# Rp2040.net
KiCad netlist of a schematic drawn in Altium Designer
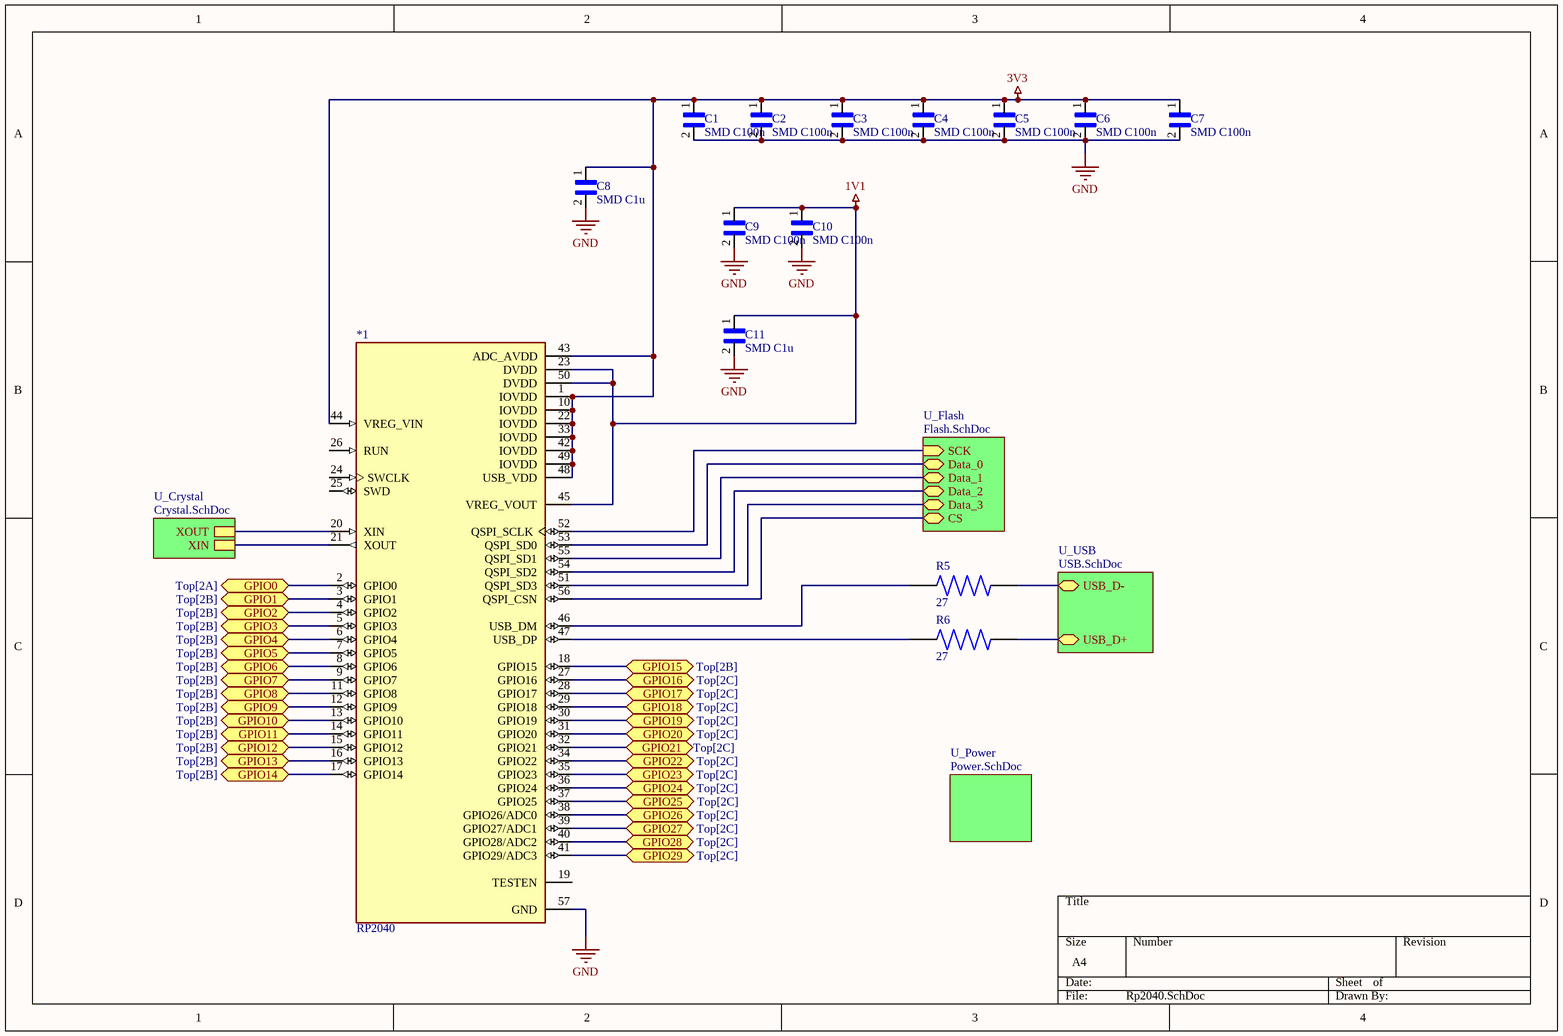
[diagram p0: Rp2040.SchDoc]

(export (version "E")
  (design (tool "Eeschema 10.0.6"))
  (components
    (comp (ref "*1")
      (value "RP2040")
      (footprint "RP2040-Footprint-1")
      (description "Microprocessor")
      (libsource (lib "Tobias") (part "RP2040-Symbol-1"))
    )
    (comp (ref "C1")
      (value "SMD C100n")
      (footprint "SMD Capacetor-Footprint-1")
      (description "Generic SMD Capacetor")
      (libsource (lib "Tobias") (part "100n"))
    )
    (comp (ref "C2")
      (value "SMD C100n")
      (footprint "SMD Capacetor-Footprint-1")
      (description "Generic SMD Capacetor")
      (libsource (lib "Tobias") (part "100n"))
    )
    (comp (ref "C3")
      (value "SMD C100n")
      (footprint "SMD Capacetor-Footprint-1")
      (description "Generic SMD Capacetor")
      (libsource (lib "Tobias") (part "100n"))
    )
    (comp (ref "C4")
      (value "SMD C100n")
      (footprint "SMD Capacetor-Footprint-1")
      (description "Generic SMD Capacetor")
      (libsource (lib "Tobias") (part "100n"))
    )
    (comp (ref "C5")
      (value "SMD C100n")
      (footprint "SMD Capacetor-Footprint-1")
      (description "Generic SMD Capacetor")
      (libsource (lib "Tobias") (part "100n"))
    )
    (comp (ref "C6")
      (value "SMD C100n")
      (footprint "SMD Capacetor-Footprint-1")
      (description "Generic SMD Capacetor")
      (libsource (lib "Tobias") (part "100n"))
    )
    (comp (ref "C7")
      (value "SMD C100n")
      (footprint "SMD Capacetor-Footprint-1")
      (description "Generic SMD Capacetor")
      (libsource (lib "Tobias") (part "100n"))
    )
    (comp (ref "C8")
      (value "SMD C1u")
      (footprint "SMD Capacetor-Footprint-1")
      (description "Generic SMD Capacetor")
      (libsource (lib "Tobias") (part "1u"))
    )
    (comp (ref "C9")
      (value "SMD C100n")
      (footprint "SMD Capacetor-Footprint-1")
      (description "Generic SMD Capacetor")
      (libsource (lib "Tobias") (part "100n"))
    )
    (comp (ref "C10")
      (value "SMD C100n")
      (footprint "SMD Capacetor-Footprint-1")
      (description "Generic SMD Capacetor")
      (libsource (lib "Tobias") (part "100n"))
    )
    (comp (ref "C11")
      (value "SMD C1u")
      (footprint "SMD Capacetor-Footprint-1")
      (description "Generic SMD Capacetor")
      (libsource (lib "Tobias") (part "1u"))
    )
    (comp (ref "R5")
      (value "27")
      (footprint "SMD Resistor-Footprint-1")
      (description "Generic SMD Resistor")
      (libsource (lib "Tobias") (part "SMD Resistor-Symbol-1"))
    )
    (comp (ref "R6")
      (value "27")
      (footprint "SMD Resistor-Footprint-1")
      (description "Generic SMD Resistor")
      (libsource (lib "Tobias") (part "SMD Resistor-Symbol-1"))
    )
  )
  (nets
    (net (code "1") (name "/CS") (class "Default")
      (node (ref "*1") (pin "56") (pinfunction "QSPI_CSN_56") (pintype "bidirectional"))
    )
    (net (code "2") (name "/Data_0") (class "Default")
      (node (ref "*1") (pin "53") (pinfunction "QSPI_SD0_53") (pintype "bidirectional"))
    )
    (net (code "3") (name "/Data_1") (class "Default")
      (node (ref "*1") (pin "55") (pinfunction "QSPI_SD1_55") (pintype "bidirectional"))
    )
    (net (code "4") (name "/Data_2") (class "Default")
      (node (ref "*1") (pin "54") (pinfunction "QSPI_SD2_54") (pintype "bidirectional"))
    )
    (net (code "5") (name "/Data_3") (class "Default")
      (node (ref "*1") (pin "51") (pinfunction "QSPI_SD3_51") (pintype "bidirectional"))
    )
    (net (code "6") (name "/GPIO0") (class "Default")
      (node (ref "*1") (pin "2") (pinfunction "GPIO0_2") (pintype "bidirectional"))
    )
    (net (code "7") (name "/GPIO1") (class "Default")
      (node (ref "*1") (pin "3") (pinfunction "GPIO1_3") (pintype "bidirectional"))
    )
    (net (code "8") (name "/GPIO2") (class "Default")
      (node (ref "*1") (pin "4") (pinfunction "GPIO2_4") (pintype "bidirectional"))
    )
    (net (code "9") (name "/GPIO3") (class "Default")
      (node (ref "*1") (pin "5") (pinfunction "GPIO3_5") (pintype "bidirectional"))
    )
    (net (code "10") (name "/GPIO4") (class "Default")
      (node (ref "*1") (pin "6") (pinfunction "GPIO4_6") (pintype "bidirectional"))
    )
    (net (code "11") (name "/GPIO5") (class "Default")
      (node (ref "*1") (pin "7") (pinfunction "GPIO5_7") (pintype "bidirectional"))
    )
    (net (code "12") (name "/GPIO6") (class "Default")
      (node (ref "*1") (pin "8") (pinfunction "GPIO6_8") (pintype "bidirectional"))
    )
    (net (code "13") (name "/GPIO7") (class "Default")
      (node (ref "*1") (pin "9") (pinfunction "GPIO7_9") (pintype "bidirectional"))
    )
    (net (code "14") (name "/GPIO8") (class "Default")
      (node (ref "*1") (pin "11") (pinfunction "GPIO8_11") (pintype "bidirectional"))
    )
    (net (code "15") (name "/GPIO9") (class "Default")
      (node (ref "*1") (pin "12") (pinfunction "GPIO9_12") (pintype "bidirectional"))
    )
    (net (code "16") (name "/GPIO10") (class "Default")
      (node (ref "*1") (pin "13") (pinfunction "GPIO10_13") (pintype "bidirectional"))
    )
    (net (code "17") (name "/GPIO11") (class "Default")
      (node (ref "*1") (pin "14") (pinfunction "GPIO11_14") (pintype "bidirectional"))
    )
    (net (code "18") (name "/GPIO12") (class "Default")
      (node (ref "*1") (pin "15") (pinfunction "GPIO12_15") (pintype "bidirectional"))
    )
    (net (code "19") (name "/GPIO13") (class "Default")
      (node (ref "*1") (pin "16") (pinfunction "GPIO13_16") (pintype "bidirectional"))
    )
    (net (code "20") (name "/GPIO14") (class "Default")
      (node (ref "*1") (pin "17") (pinfunction "GPIO14_17") (pintype "bidirectional"))
    )
    (net (code "21") (name "/GPIO15") (class "Default")
      (node (ref "*1") (pin "18") (pinfunction "GPIO15_18") (pintype "bidirectional"))
    )
    (net (code "22") (name "/GPIO16") (class "Default")
      (node (ref "*1") (pin "27") (pinfunction "GPIO16_27") (pintype "bidirectional"))
    )
    (net (code "23") (name "/GPIO17") (class "Default")
      (node (ref "*1") (pin "28") (pinfunction "GPIO17_28") (pintype "bidirectional"))
    )
    (net (code "24") (name "/GPIO18") (class "Default")
      (node (ref "*1") (pin "29") (pinfunction "GPIO18_29") (pintype "bidirectional"))
    )
    (net (code "25") (name "/GPIO19") (class "Default")
      (node (ref "*1") (pin "30") (pinfunction "GPIO19_30") (pintype "bidirectional"))
    )
    (net (code "26") (name "/GPIO20") (class "Default")
      (node (ref "*1") (pin "31") (pinfunction "GPIO20_31") (pintype "bidirectional"))
    )
    (net (code "27") (name "/GPIO21") (class "Default")
      (node (ref "*1") (pin "32") (pinfunction "GPIO21_32") (pintype "bidirectional"))
    )
    (net (code "28") (name "/GPIO22") (class "Default")
      (node (ref "*1") (pin "34") (pinfunction "GPIO22_34") (pintype "bidirectional"))
    )
    (net (code "29") (name "/GPIO23") (class "Default")
      (node (ref "*1") (pin "35") (pinfunction "GPIO23_35") (pintype "bidirectional"))
    )
    (net (code "30") (name "/GPIO24") (class "Default")
      (node (ref "*1") (pin "36") (pinfunction "GPIO24_36") (pintype "bidirectional"))
    )
    (net (code "31") (name "/GPIO25") (class "Default")
      (node (ref "*1") (pin "37") (pinfunction "GPIO25_37") (pintype "bidirectional"))
    )
    (net (code "32") (name "/GPIO26") (class "Default")
      (node (ref "*1") (pin "38") (pinfunction "GPIO26/ADC0_38") (pintype "bidirectional"))
    )
    (net (code "33") (name "/GPIO27") (class "Default")
      (node (ref "*1") (pin "39") (pinfunction "GPIO27/ADC1_39") (pintype "bidirectional"))
    )
    (net (code "34") (name "/GPIO28") (class "Default")
      (node (ref "*1") (pin "40") (pinfunction "GPIO28/ADC2_40") (pintype "bidirectional"))
    )
    (net (code "35") (name "/GPIO29") (class "Default")
      (node (ref "*1") (pin "41") (pinfunction "GPIO29/ADC3_41") (pintype "bidirectional"))
    )
    (net (code "36") (name "/SCK") (class "Default")
      (node (ref "*1") (pin "52") (pinfunction "QSPI_SCLK_52") (pintype "bidirectional"))
    )
    (net (code "37") (name "/USB_D+") (class "Default")
      (node (ref "R6") (pin "2") (pinfunction "2_2") (pintype "passive"))
    )
    (net (code "38") (name "/USB_D-") (class "Default")
      (node (ref "R5") (pin "2") (pinfunction "2_2") (pintype "passive"))
    )
    (net (code "39") (name "/XIN") (class "Default")
      (node (ref "*1") (pin "21") (pinfunction "XOUT_21") (pintype "output"))
    )
    (net (code "40") (name "/XOUT") (class "Default")
      (node (ref "*1") (pin "20") (pinfunction "XIN_20") (pintype "input"))
    )
    (net (code "41") (name "1V1") (class "Default")
      (node (ref "*1") (pin "23") (pinfunction "DVDD_23") (pintype "power_in"))
      (node (ref "*1") (pin "45") (pinfunction "VREG_VOUT_45") (pintype "power_in"))
      (node (ref "*1") (pin "50") (pinfunction "DVDD_50") (pintype "power_in"))
      (node (ref "C10") (pin "1") (pinfunction "1_1") (pintype "passive"))
      (node (ref "C11") (pin "1") (pinfunction "1_1") (pintype "passive"))
      (node (ref "C9") (pin "1") (pinfunction "1_1") (pintype "passive"))
    )
    (net (code "42") (name "3V3") (class "Default")
      (node (ref "*1") (pin "1") (pinfunction "IOVDD_1") (pintype "power_in"))
      (node (ref "*1") (pin "10") (pinfunction "IOVDD_10") (pintype "power_in"))
      (node (ref "*1") (pin "22") (pinfunction "IOVDD_22") (pintype "power_in"))
      (node (ref "*1") (pin "33") (pinfunction "IOVDD_33") (pintype "power_in"))
      (node (ref "*1") (pin "42") (pinfunction "IOVDD_42") (pintype "power_in"))
      (node (ref "*1") (pin "43") (pinfunction "ADC_AVDD_43") (pintype "power_in"))
      (node (ref "*1") (pin "44") (pinfunction "VREG_VIN_44") (pintype "input"))
      (node (ref "*1") (pin "48") (pinfunction "USB_VDD_48") (pintype "power_in"))
      (node (ref "*1") (pin "49") (pinfunction "IOVDD_49") (pintype "power_in"))
      (node (ref "C1") (pin "1") (pinfunction "1_1") (pintype "passive"))
      (node (ref "C2") (pin "1") (pinfunction "1_1") (pintype "passive"))
      (node (ref "C3") (pin "1") (pinfunction "1_1") (pintype "passive"))
      (node (ref "C4") (pin "1") (pinfunction "1_1") (pintype "passive"))
      (node (ref "C5") (pin "1") (pinfunction "1_1") (pintype "passive"))
      (node (ref "C6") (pin "1") (pinfunction "1_1") (pintype "passive"))
      (node (ref "C7") (pin "1") (pinfunction "1_1") (pintype "passive"))
      (node (ref "C8") (pin "1") (pinfunction "1_1") (pintype "passive"))
    )
    (net (code "43") (name "GND") (class "Default")
      (node (ref "*1") (pin "57") (pinfunction "GND_57") (pintype "power_in"))
      (node (ref "C1") (pin "2") (pinfunction "2_2") (pintype "passive"))
      (node (ref "C10") (pin "2") (pinfunction "2_2") (pintype "passive"))
      (node (ref "C11") (pin "2") (pinfunction "2_2") (pintype "passive"))
      (node (ref "C2") (pin "2") (pinfunction "2_2") (pintype "passive"))
      (node (ref "C3") (pin "2") (pinfunction "2_2") (pintype "passive"))
      (node (ref "C4") (pin "2") (pinfunction "2_2") (pintype "passive"))
      (node (ref "C5") (pin "2") (pinfunction "2_2") (pintype "passive"))
      (node (ref "C6") (pin "2") (pinfunction "2_2") (pintype "passive"))
      (node (ref "C7") (pin "2") (pinfunction "2_2") (pintype "passive"))
      (node (ref "C8") (pin "2") (pinfunction "2_2") (pintype "passive"))
      (node (ref "C9") (pin "2") (pinfunction "2_2") (pintype "passive"))
    )
    (net (code "44") (name "Net-(*1-USB_DM)") (class "Default")
      (node (ref "*1") (pin "46") (pinfunction "USB_DM_46") (pintype "bidirectional"))
      (node (ref "R5") (pin "1") (pinfunction "1_1") (pintype "passive"))
    )
    (net (code "45") (name "Net-(*1-USB_DP)") (class "Default")
      (node (ref "*1") (pin "47") (pinfunction "USB_DP_47") (pintype "bidirectional"))
      (node (ref "R6") (pin "1") (pinfunction "1_1") (pintype "passive"))
    )
    (net (code "46") (name "unconnected-(*1-RUN-Pad26)") (class "Default")
      (node (ref "*1") (pin "26") (pinfunction "RUN_26") (pintype "input"))
    )
    (net (code "47") (name "unconnected-(*1-SWCLK-Pad24)") (class "Default")
      (node (ref "*1") (pin "24") (pinfunction "SWCLK_24") (pintype "input"))
    )
    (net (code "48") (name "unconnected-(*1-SWD-Pad25)") (class "Default")
      (node (ref "*1") (pin "25") (pinfunction "SWD_25") (pintype "bidirectional"))
    )
    (net (code "49") (name "unconnected-(*1-TESTEN-Pad19)") (class "Default")
      (node (ref "*1") (pin "19") (pinfunction "TESTEN_19") (pintype "passive"))
    )
  )
)
